# DS18B20Test4.net
KiCad netlist of a schematic drawn in EAGLE
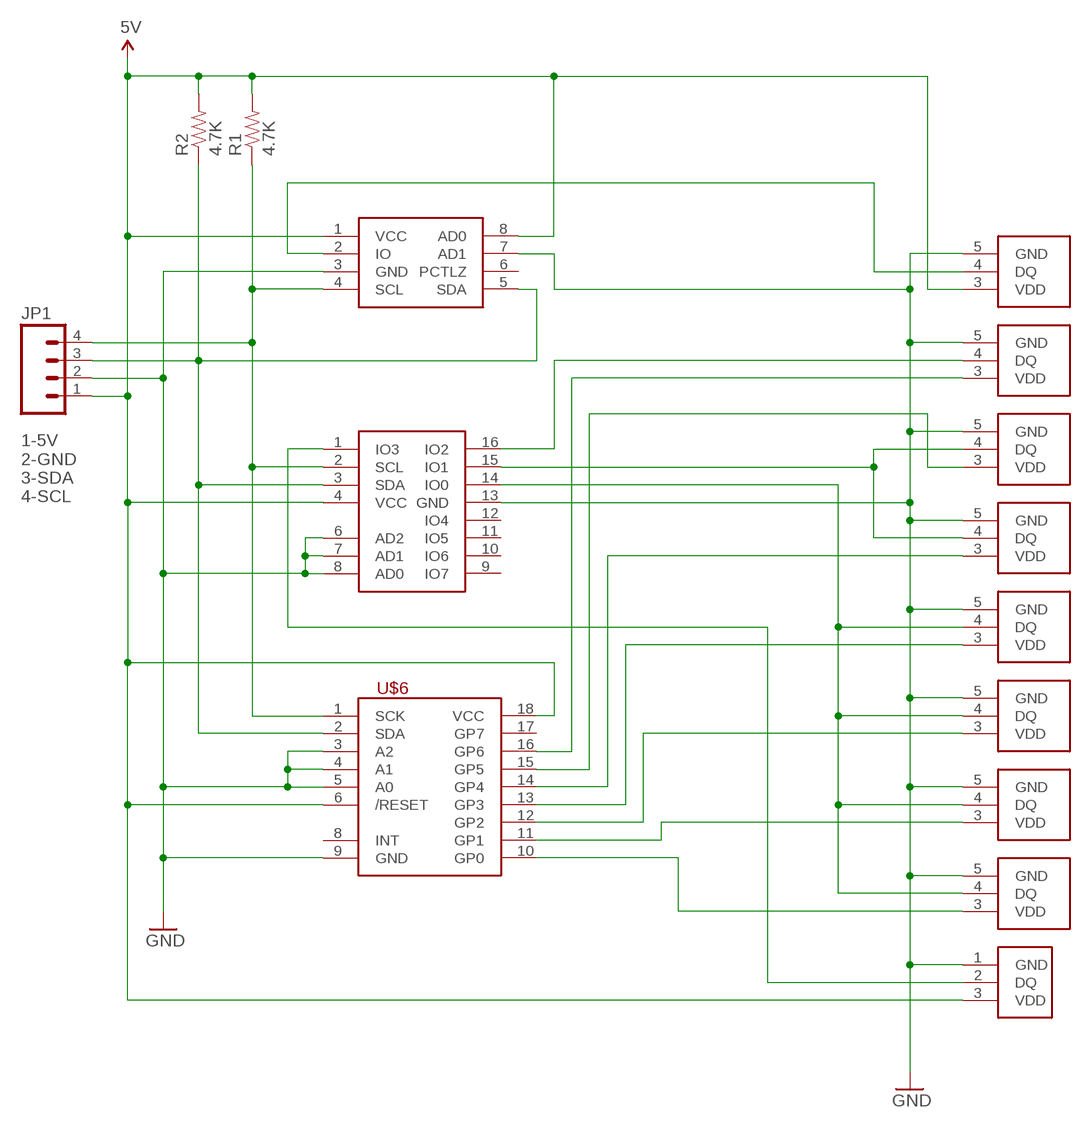
[diagram p0: schematic, sheet 1]

(export (version "E")
  (design (tool "Eeschema 10.0.6"))
  (components
    (comp (ref "JP1")
      (value "M04PTH")
      (footprint "eagle-import:1X04")
      (libsource (lib "eagle-import") (part "M04PTH"))
    )
    (comp (ref "R1")
      (value "4.7K")
      (footprint "eagle-import:0603-RES")
      (libsource (lib "eagle-import") (part "RES-4.7K-0603"))
    )
    (comp (ref "R2")
      (value "4.7K")
      (footprint "eagle-import:0603-RES")
      (libsource (lib "eagle-import") (part "RES-4.7K-0603"))
    )
    (comp (ref "U$1")
      (value "DS2482-100")
      (footprint "eagle-import:8-SOIC-MAXIM")
      (libsource (lib "eagle-import") (part "DS2482-100"))
    )
    (comp (ref "U$2")
      (value "DS2482-800")
      (footprint "eagle-import:16-SOIC-MAXIM")
      (libsource (lib "eagle-import") (part "DS2482-800"))
    )
    (comp (ref "U$3")
      (value "TERMBLOCK-1WIRE")
      (footprint "eagle-import:TERMBLOCK-1WIRE")
      (libsource (lib "eagle-import") (part "TERMBLOCK-1WIRE"))
    )
    (comp (ref "U$4")
      (value "DS18B208-SOIC")
      (footprint "eagle-import:DS18B20-S0")
      (libsource (lib "eagle-import") (part "DS18B208-SOIC"))
    )
    (comp (ref "U$5")
      (value "DS18B208-SOIC")
      (footprint "eagle-import:DS18B20-S0")
      (libsource (lib "eagle-import") (part "DS18B208-SOIC"))
    )
    (comp (ref "U$6")
      (value "MCP23008")
      (footprint "eagle-import:SOIC-18-W-MAXIM")
      (libsource (lib "eagle-import") (part "MCP23008"))
    )
    (comp (ref "U$7")
      (value "DS18B208-SOIC")
      (footprint "eagle-import:DS18B20-S0")
      (libsource (lib "eagle-import") (part "DS18B208-SOIC"))
    )
    (comp (ref "U$8")
      (value "DS18B208-SOIC")
      (footprint "eagle-import:DS18B20-S0")
      (libsource (lib "eagle-import") (part "DS18B208-SOIC"))
    )
    (comp (ref "U$9")
      (value "DS18B208-SOIC")
      (footprint "eagle-import:DS18B20-S0")
      (libsource (lib "eagle-import") (part "DS18B208-SOIC"))
    )
    (comp (ref "U$10")
      (value "DS18B208-SOIC")
      (footprint "eagle-import:DS18B20-S0")
      (libsource (lib "eagle-import") (part "DS18B208-SOIC"))
    )
    (comp (ref "U$11")
      (value "DS18B208-SOIC")
      (footprint "eagle-import:DS18B20-S0")
      (libsource (lib "eagle-import") (part "DS18B208-SOIC"))
    )
    (comp (ref "U$12")
      (value "DS18B208-SOIC")
      (footprint "eagle-import:DS18B20-S0")
      (libsource (lib "eagle-import") (part "DS18B208-SOIC"))
    )
  )
  (nets
    (net (code "1") (name "5V") (class "Default")
      (node (ref "JP1") (pin "1") (pinfunction "1_1") (pintype "passive"))
      (node (ref "R1") (pin "2") (pinfunction "2_2") (pintype "passive"))
      (node (ref "R2") (pin "2") (pinfunction "2_2") (pintype "passive"))
      (node (ref "U$1") (pin "1") (pinfunction "VCC_1") (pintype "power_in"))
      (node (ref "U$1") (pin "8") (pinfunction "AD0_8") (pintype "input"))
      (node (ref "U$2") (pin "4") (pinfunction "VCC_4") (pintype "power_in"))
      (node (ref "U$3") (pin "3") (pinfunction "VDD_3") (pintype "power_in"))
      (node (ref "U$4") (pin "3") (pinfunction "VDD_3") (pintype "power_in"))
      (node (ref "U$6") (pin "18") (pinfunction "VCC_18") (pintype "passive"))
      (node (ref "U$6") (pin "6") (pinfunction "/RESET_6") (pintype "input"))
    )
    (net (code "2") (name "GND") (class "Default")
      (node (ref "JP1") (pin "2") (pinfunction "2_2") (pintype "passive"))
      (node (ref "U$1") (pin "3") (pinfunction "GND_3") (pintype "power_in"))
      (node (ref "U$1") (pin "7") (pinfunction "AD1_7") (pintype "input"))
      (node (ref "U$10") (pin "5") (pinfunction "GND_5") (pintype "power_in"))
      (node (ref "U$11") (pin "5") (pinfunction "GND_5") (pintype "power_in"))
      (node (ref "U$12") (pin "5") (pinfunction "GND_5") (pintype "power_in"))
      (node (ref "U$2") (pin "13") (pinfunction "GND_13") (pintype "power_in"))
      (node (ref "U$2") (pin "6") (pinfunction "AD2_6") (pintype "input"))
      (node (ref "U$2") (pin "7") (pinfunction "AD1_7") (pintype "input"))
      (node (ref "U$2") (pin "8") (pinfunction "AD0_8") (pintype "input"))
      (node (ref "U$3") (pin "1") (pinfunction "GND_1") (pintype "power_in"))
      (node (ref "U$4") (pin "5") (pinfunction "GND_5") (pintype "power_in"))
      (node (ref "U$5") (pin "5") (pinfunction "GND_5") (pintype "power_in"))
      (node (ref "U$6") (pin "3") (pinfunction "A2_3") (pintype "input"))
      (node (ref "U$6") (pin "4") (pinfunction "A1_4") (pintype "input"))
      (node (ref "U$6") (pin "5") (pinfunction "A0_5") (pintype "bidirectional"))
      (node (ref "U$6") (pin "9") (pinfunction "GND_9") (pintype "passive"))
      (node (ref "U$7") (pin "5") (pinfunction "GND_5") (pintype "power_in"))
      (node (ref "U$8") (pin "5") (pinfunction "GND_5") (pintype "power_in"))
      (node (ref "U$9") (pin "5") (pinfunction "GND_5") (pintype "power_in"))
    )
    (net (code "3") (name "Net-(U$1-IO)") (class "Default")
      (node (ref "U$1") (pin "2") (pinfunction "IO_2") (pintype "bidirectional"))
      (node (ref "U$4") (pin "4") (pinfunction "DQ_4") (pintype "bidirectional"))
    )
    (net (code "4") (name "Net-(U$1-SCL)") (class "Default")
      (node (ref "JP1") (pin "4") (pinfunction "4_4") (pintype "passive"))
      (node (ref "R1") (pin "1") (pinfunction "1_1") (pintype "passive"))
      (node (ref "U$1") (pin "4") (pinfunction "SCL_4") (pintype "bidirectional"))
      (node (ref "U$2") (pin "2") (pinfunction "SCL_2") (pintype "bidirectional"))
      (node (ref "U$6") (pin "1") (pinfunction "SCK_1") (pintype "input"))
    )
    (net (code "5") (name "Net-(U$1-SDA)") (class "Default")
      (node (ref "JP1") (pin "3") (pinfunction "3_3") (pintype "passive"))
      (node (ref "R2") (pin "1") (pinfunction "1_1") (pintype "passive"))
      (node (ref "U$1") (pin "5") (pinfunction "SDA_5") (pintype "bidirectional"))
      (node (ref "U$2") (pin "3") (pinfunction "SDA_3") (pintype "bidirectional"))
      (node (ref "U$6") (pin "2") (pinfunction "SDA_2") (pintype "bidirectional"))
    )
    (net (code "6") (name "Net-(U$2-IO1)") (class "Default")
      (node (ref "U$2") (pin "15") (pinfunction "IO1_15") (pintype "bidirectional"))
      (node (ref "U$7") (pin "4") (pinfunction "DQ_4") (pintype "bidirectional"))
      (node (ref "U$8") (pin "4") (pinfunction "DQ_4") (pintype "bidirectional"))
    )
    (net (code "7") (name "Net-(U$2-IO2)") (class "Default")
      (node (ref "U$2") (pin "16") (pinfunction "IO2_16") (pintype "bidirectional"))
      (node (ref "U$5") (pin "4") (pinfunction "DQ_4") (pintype "bidirectional"))
    )
    (net (code "8") (name "Net-(U$2-IO3)") (class "Default")
      (node (ref "U$2") (pin "1") (pinfunction "IO3_1") (pintype "bidirectional"))
      (node (ref "U$3") (pin "2") (pinfunction "DQ_2") (pintype "bidirectional"))
    )
    (net (code "9") (name "Net-(U$5-VDD)") (class "Default")
      (node (ref "U$5") (pin "3") (pinfunction "VDD_3") (pintype "power_in"))
      (node (ref "U$6") (pin "16") (pinfunction "GP6_16") (pintype "bidirectional"))
    )
    (net (code "10") (name "Net-(U$6-GP3)") (class "Default")
      (node (ref "U$6") (pin "13") (pinfunction "GP3_13") (pintype "bidirectional"))
      (node (ref "U$9") (pin "3") (pinfunction "VDD_3") (pintype "power_in"))
    )
    (net (code "11") (name "Net-(U$6-GP4)") (class "Default")
      (node (ref "U$6") (pin "14") (pinfunction "GP4_14") (pintype "bidirectional"))
      (node (ref "U$8") (pin "3") (pinfunction "VDD_3") (pintype "power_in"))
    )
    (net (code "12") (name "Net-(U$6-GP5)") (class "Default")
      (node (ref "U$6") (pin "15") (pinfunction "GP5_15") (pintype "bidirectional"))
      (node (ref "U$7") (pin "3") (pinfunction "VDD_3") (pintype "power_in"))
    )
    (net (code "13") (name "Net-(U$10-DQ)") (class "Default")
      (node (ref "U$10") (pin "4") (pinfunction "DQ_4") (pintype "bidirectional"))
      (node (ref "U$11") (pin "4") (pinfunction "DQ_4") (pintype "bidirectional"))
      (node (ref "U$12") (pin "4") (pinfunction "DQ_4") (pintype "bidirectional"))
      (node (ref "U$2") (pin "14") (pinfunction "IO0_14") (pintype "bidirectional"))
      (node (ref "U$9") (pin "4") (pinfunction "DQ_4") (pintype "bidirectional"))
    )
    (net (code "14") (name "Net-(U$10-VDD)") (class "Default")
      (node (ref "U$10") (pin "3") (pinfunction "VDD_3") (pintype "power_in"))
      (node (ref "U$6") (pin "12") (pinfunction "GP2_12") (pintype "bidirectional"))
    )
    (net (code "15") (name "Net-(U$11-VDD)") (class "Default")
      (node (ref "U$11") (pin "3") (pinfunction "VDD_3") (pintype "power_in"))
      (node (ref "U$6") (pin "11") (pinfunction "GP1_11") (pintype "bidirectional"))
    )
    (net (code "16") (name "Net-(U$12-VDD)") (class "Default")
      (node (ref "U$12") (pin "3") (pinfunction "VDD_3") (pintype "power_in"))
      (node (ref "U$6") (pin "10") (pinfunction "GP0_10") (pintype "bidirectional"))
    )
    (net (code "17") (name "unconnected-(U$1-PCTLZ-Pad6)") (class "Default")
      (node (ref "U$1") (pin "6") (pinfunction "PCTLZ_6") (pintype "output"))
    )
    (net (code "18") (name "unconnected-(U$2-IO4-Pad12)") (class "Default")
      (node (ref "U$2") (pin "12") (pinfunction "IO4_12") (pintype "bidirectional"))
    )
    (net (code "19") (name "unconnected-(U$2-IO5-Pad11)") (class "Default")
      (node (ref "U$2") (pin "11") (pinfunction "IO5_11") (pintype "bidirectional"))
    )
    (net (code "20") (name "unconnected-(U$2-IO6-Pad10)") (class "Default")
      (node (ref "U$2") (pin "10") (pinfunction "IO6_10") (pintype "bidirectional"))
    )
    (net (code "21") (name "unconnected-(U$2-IO7-Pad9)") (class "Default")
      (node (ref "U$2") (pin "9") (pinfunction "IO7_9") (pintype "bidirectional"))
    )
    (net (code "22") (name "unconnected-(U$6-GP7-Pad17)") (class "Default")
      (node (ref "U$6") (pin "17") (pinfunction "GP7_17") (pintype "bidirectional"))
    )
    (net (code "23") (name "unconnected-(U$6-INT-Pad8)") (class "Default")
      (node (ref "U$6") (pin "8") (pinfunction "INT_8") (pintype "output"))
    )
  )
)
